# Buck_Regulator.net
KiCad netlist of a schematic drawn in EAGLE
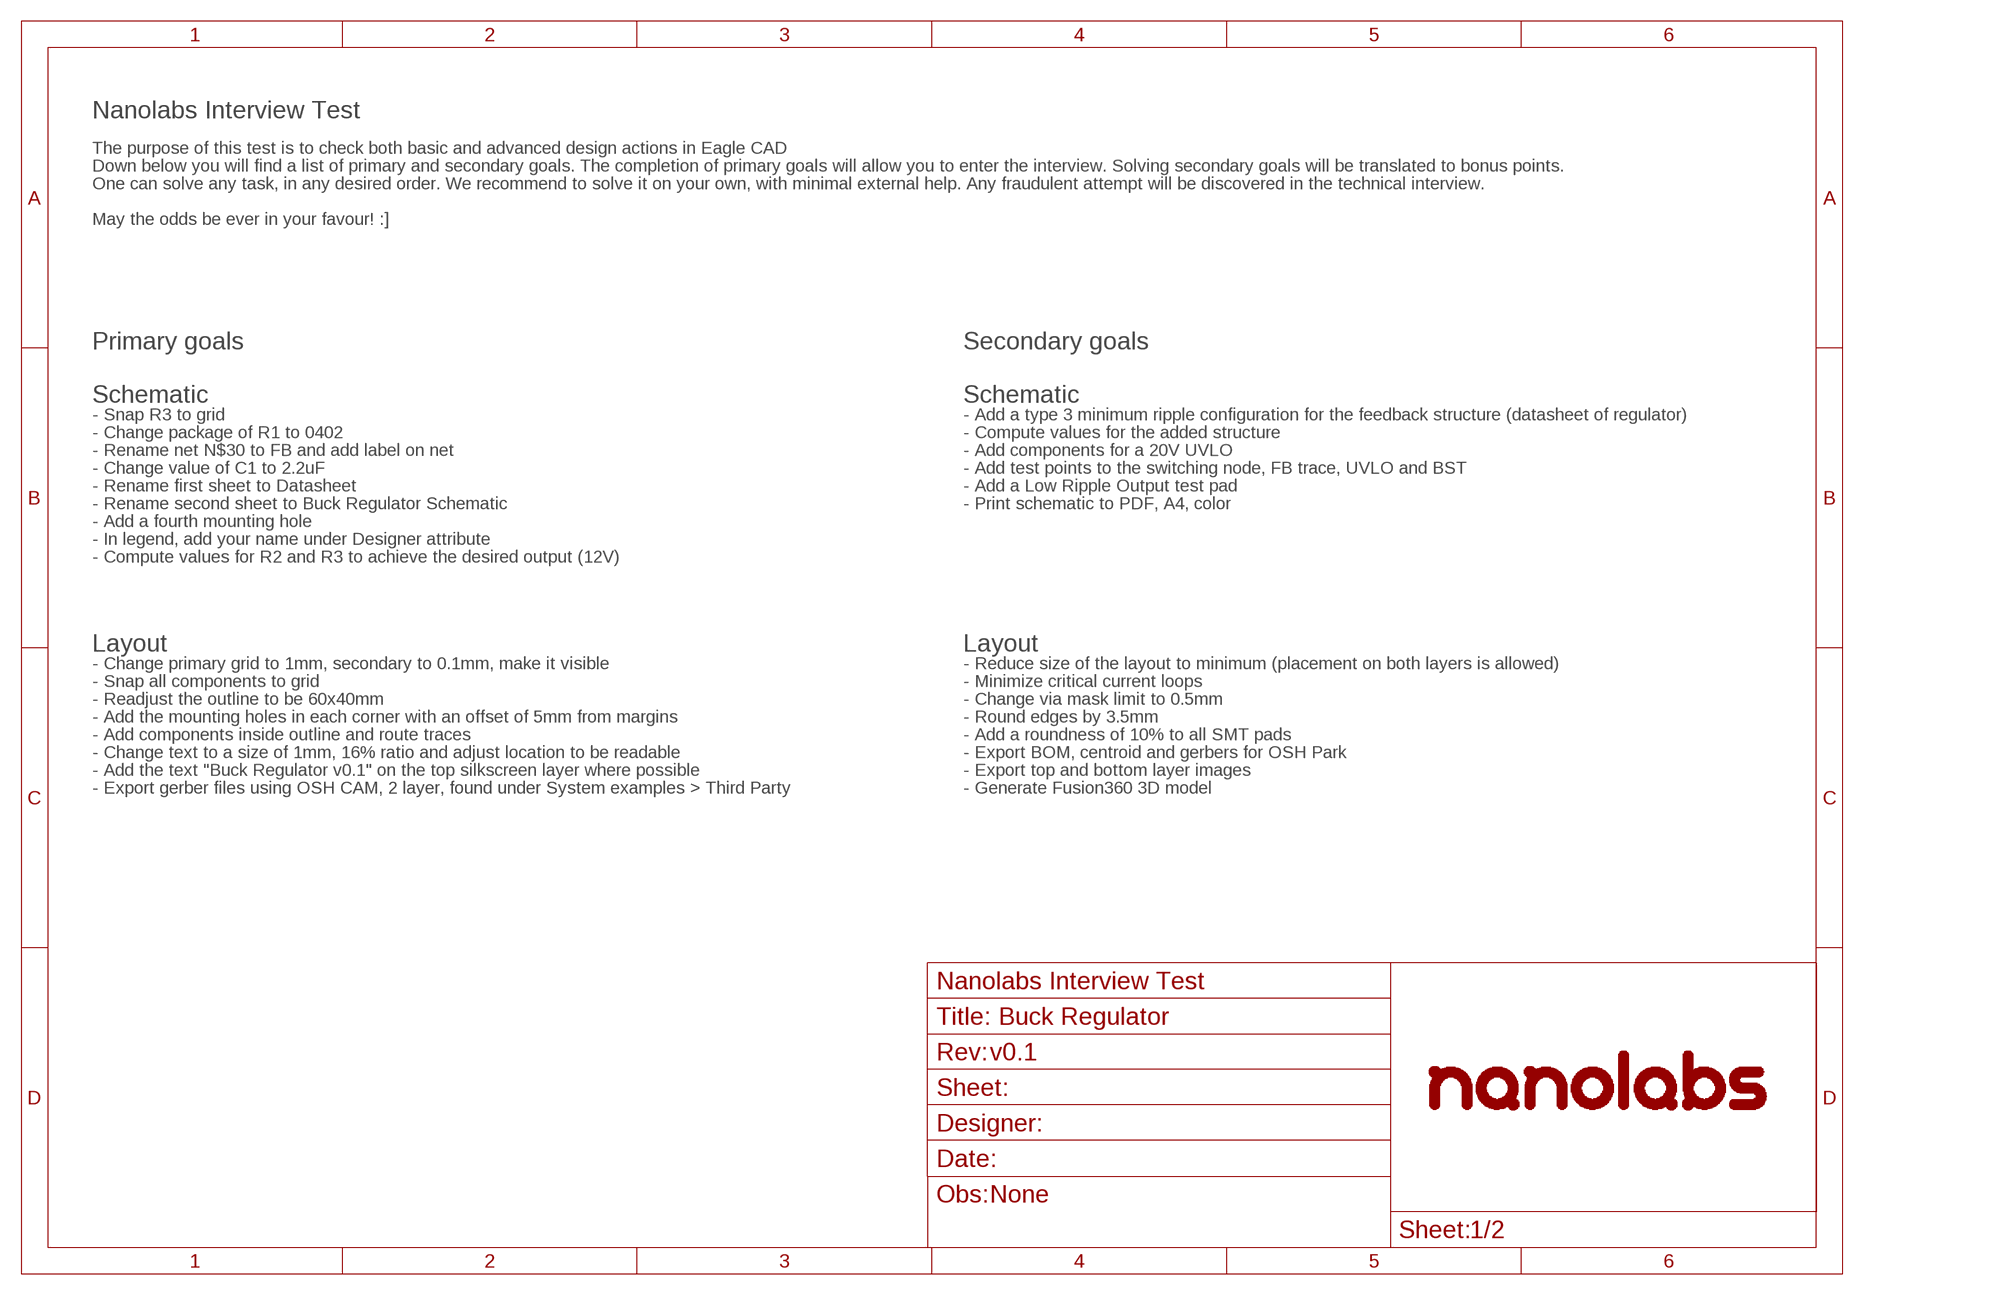
[diagram p0: schematic, sheet 1]
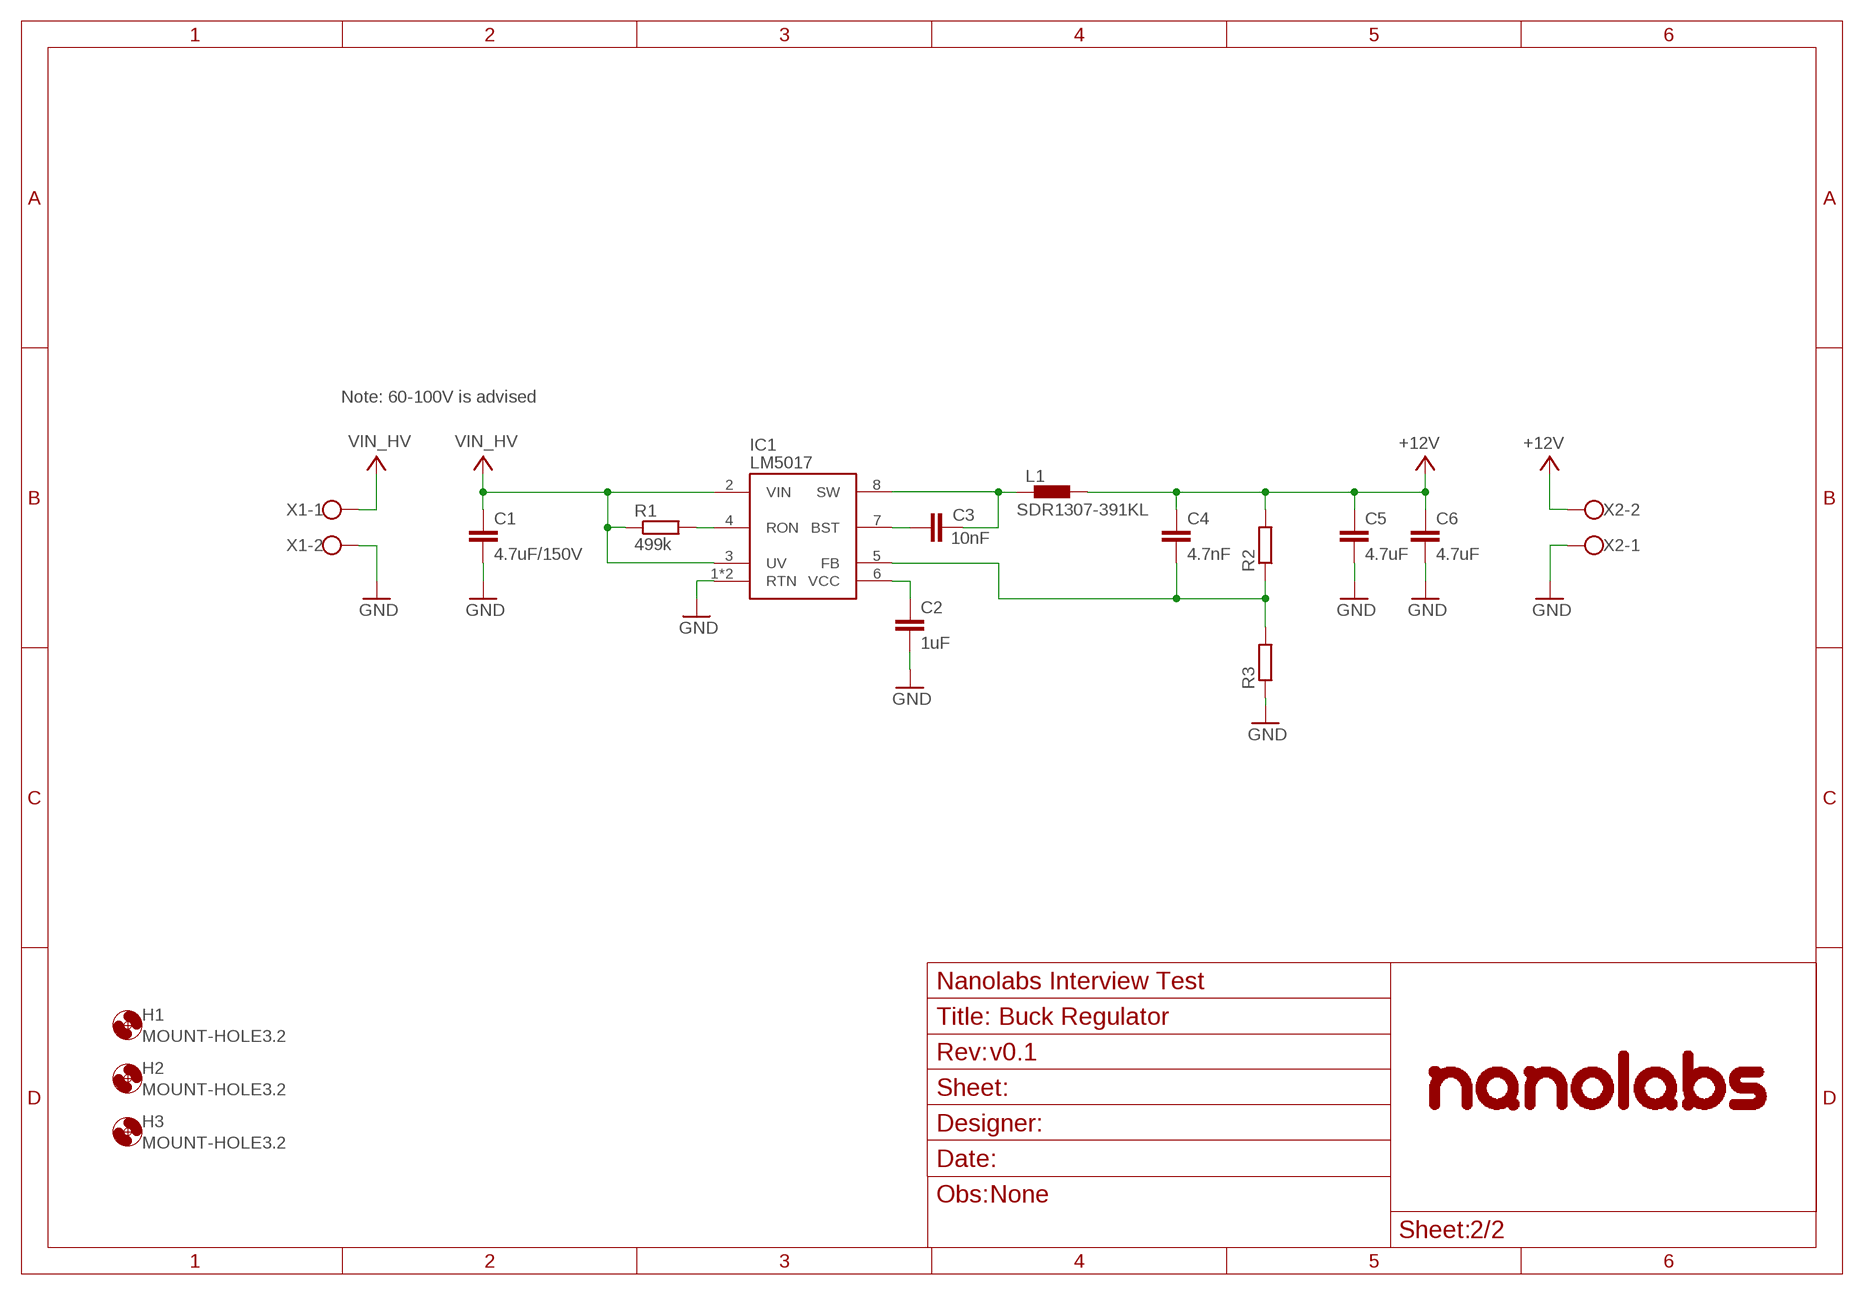
[diagram p1: schematic, sheet 2]

(export (version "E")
  (design (tool "Eeschema 10.0.6"))
  (components
    (comp (ref "C1")
      (value "4.7uF/150V")
      (footprint "eagle-import:C1812")
      (libsource (lib "eagle-import") (part "C-EUC1812"))
    )
    (comp (ref "C2")
      (value "1uF")
      (footprint "eagle-import:C0603")
      (libsource (lib "eagle-import") (part "C-EUC0603"))
    )
    (comp (ref "C3")
      (value "10nF")
      (footprint "eagle-import:C0603")
      (libsource (lib "eagle-import") (part "C-EUC0603"))
    )
    (comp (ref "C4")
      (value "4.7nF")
      (footprint "eagle-import:C0603")
      (libsource (lib "eagle-import") (part "C-EUC0603"))
    )
    (comp (ref "C5")
      (value "4.7uF")
      (footprint "eagle-import:C0603")
      (libsource (lib "eagle-import") (part "C-EUC0603"))
    )
    (comp (ref "C6")
      (value "4.7uF")
      (footprint "eagle-import:C0603")
      (libsource (lib "eagle-import") (part "C-EUC0603"))
    )
    (comp (ref "H1")
      (value "MOUNT-HOLE3.2")
      (footprint "eagle-import:3,2")
      (libsource (lib "eagle-import") (part "MOUNT-HOLE3.2"))
    )
    (comp (ref "H2")
      (value "MOUNT-HOLE3.2")
      (footprint "eagle-import:3,2")
      (libsource (lib "eagle-import") (part "MOUNT-HOLE3.2"))
    )
    (comp (ref "H3")
      (value "MOUNT-HOLE3.2")
      (footprint "eagle-import:3,2")
      (libsource (lib "eagle-import") (part "MOUNT-HOLE3.2"))
    )
    (comp (ref "IC1")
      (value "LM5017")
      (footprint "eagle-import:SO-08-EP")
      (libsource (lib "eagle-import") (part "LM5017"))
    )
    (comp (ref "L1")
      (value "SDR1307-391KL")
      (footprint "eagle-import:SDR1307-391KL")
      (libsource (lib "eagle-import") (part "SDR1307-391KL"))
    )
    (comp (ref "R1")
      (value "499k")
      (footprint "eagle-import:R0603")
      (libsource (lib "eagle-import") (part "R-EU_R0603"))
    )
    (comp (ref "R2")
      (value "R-EU_R0603")
      (footprint "eagle-import:R0603")
      (libsource (lib "eagle-import") (part "R-EU_R0603"))
    )
    (comp (ref "R3")
      (value "R-EU_R0603")
      (footprint "eagle-import:R0603")
      (libsource (lib "eagle-import") (part "R-EU_R0603"))
    )
    (comp (ref "X1")
      (value "W237-102")
      (footprint "eagle-import:W237-102")
      (fields (field (name "MPN") "237-102"))
      (libsource (lib "eagle-import") (part "W237-102"))
    )
    (comp (ref "X2")
      (value "W237-102")
      (footprint "eagle-import:W237-102")
      (fields (field (name "MPN") "237-102"))
      (libsource (lib "eagle-import") (part "W237-102"))
    )
  )
  (nets
    (net (code "1") (name "+12V") (class "Default")
      (node (ref "C4") (pin "1") (pinfunction "1_1") (pintype "passive"))
      (node (ref "C5") (pin "1") (pinfunction "1_1") (pintype "passive"))
      (node (ref "C6") (pin "1") (pinfunction "1_1") (pintype "passive"))
      (node (ref "L1") (pin "2") (pinfunction "2_2") (pintype "passive"))
      (node (ref "R2") (pin "2") (pinfunction "2_2") (pintype "passive"))
      (node (ref "X2") (pin "2") (pinfunction "KL_2") (pintype "passive"))
    )
    (net (code "2") (name "GND") (class "Default")
      (node (ref "C1") (pin "2") (pinfunction "2_2") (pintype "passive"))
      (node (ref "C2") (pin "2") (pinfunction "2_2") (pintype "passive"))
      (node (ref "C5") (pin "2") (pinfunction "2_2") (pintype "passive"))
      (node (ref "C6") (pin "2") (pinfunction "2_2") (pintype "passive"))
      (node (ref "IC1") (pin "1") (pinfunction "RTN_1") (pintype "bidirectional"))
      (node (ref "IC1") (pin "9") (pinfunction "RTN_9") (pintype "bidirectional"))
      (node (ref "R3") (pin "1") (pinfunction "1_1") (pintype "passive"))
      (node (ref "X1") (pin "2") (pinfunction "KL_2") (pintype "passive"))
      (node (ref "X2") (pin "1") (pinfunction "KL_1") (pintype "passive"))
    )
    (net (code "3") (name "Net-(IC1-BST)") (class "Default")
      (node (ref "C3") (pin "1") (pinfunction "1_1") (pintype "passive"))
      (node (ref "IC1") (pin "7") (pinfunction "BST_7") (pintype "bidirectional"))
    )
    (net (code "4") (name "Net-(IC1-FB)") (class "Default")
      (node (ref "C4") (pin "2") (pinfunction "2_2") (pintype "passive"))
      (node (ref "IC1") (pin "5") (pinfunction "FB_5") (pintype "bidirectional"))
      (node (ref "R2") (pin "1") (pinfunction "1_1") (pintype "passive"))
      (node (ref "R3") (pin "2") (pinfunction "2_2") (pintype "passive"))
    )
    (net (code "5") (name "Net-(IC1-RON)") (class "Default")
      (node (ref "IC1") (pin "4") (pinfunction "RON_4") (pintype "bidirectional"))
      (node (ref "R1") (pin "2") (pinfunction "2_2") (pintype "passive"))
    )
    (net (code "6") (name "Net-(IC1-SW)") (class "Default")
      (node (ref "C3") (pin "2") (pinfunction "2_2") (pintype "passive"))
      (node (ref "IC1") (pin "8") (pinfunction "SW_8") (pintype "bidirectional"))
      (node (ref "L1") (pin "1") (pinfunction "1_1") (pintype "passive"))
    )
    (net (code "7") (name "Net-(IC1-VCC)") (class "Default")
      (node (ref "C2") (pin "1") (pinfunction "1_1") (pintype "passive"))
      (node (ref "IC1") (pin "6") (pinfunction "VCC_6") (pintype "bidirectional"))
    )
    (net (code "8") (name "VIN_HV") (class "Default")
      (node (ref "C1") (pin "1") (pinfunction "1_1") (pintype "passive"))
      (node (ref "IC1") (pin "2") (pinfunction "VIN_2") (pintype "bidirectional"))
      (node (ref "IC1") (pin "3") (pinfunction "UV_3") (pintype "bidirectional"))
      (node (ref "R1") (pin "1") (pinfunction "1_1") (pintype "passive"))
      (node (ref "X1") (pin "1") (pinfunction "KL_1") (pintype "passive"))
    )
  )
)
